# DAC_0.net
KiCad netlist of a schematic drawn in Altium Designer
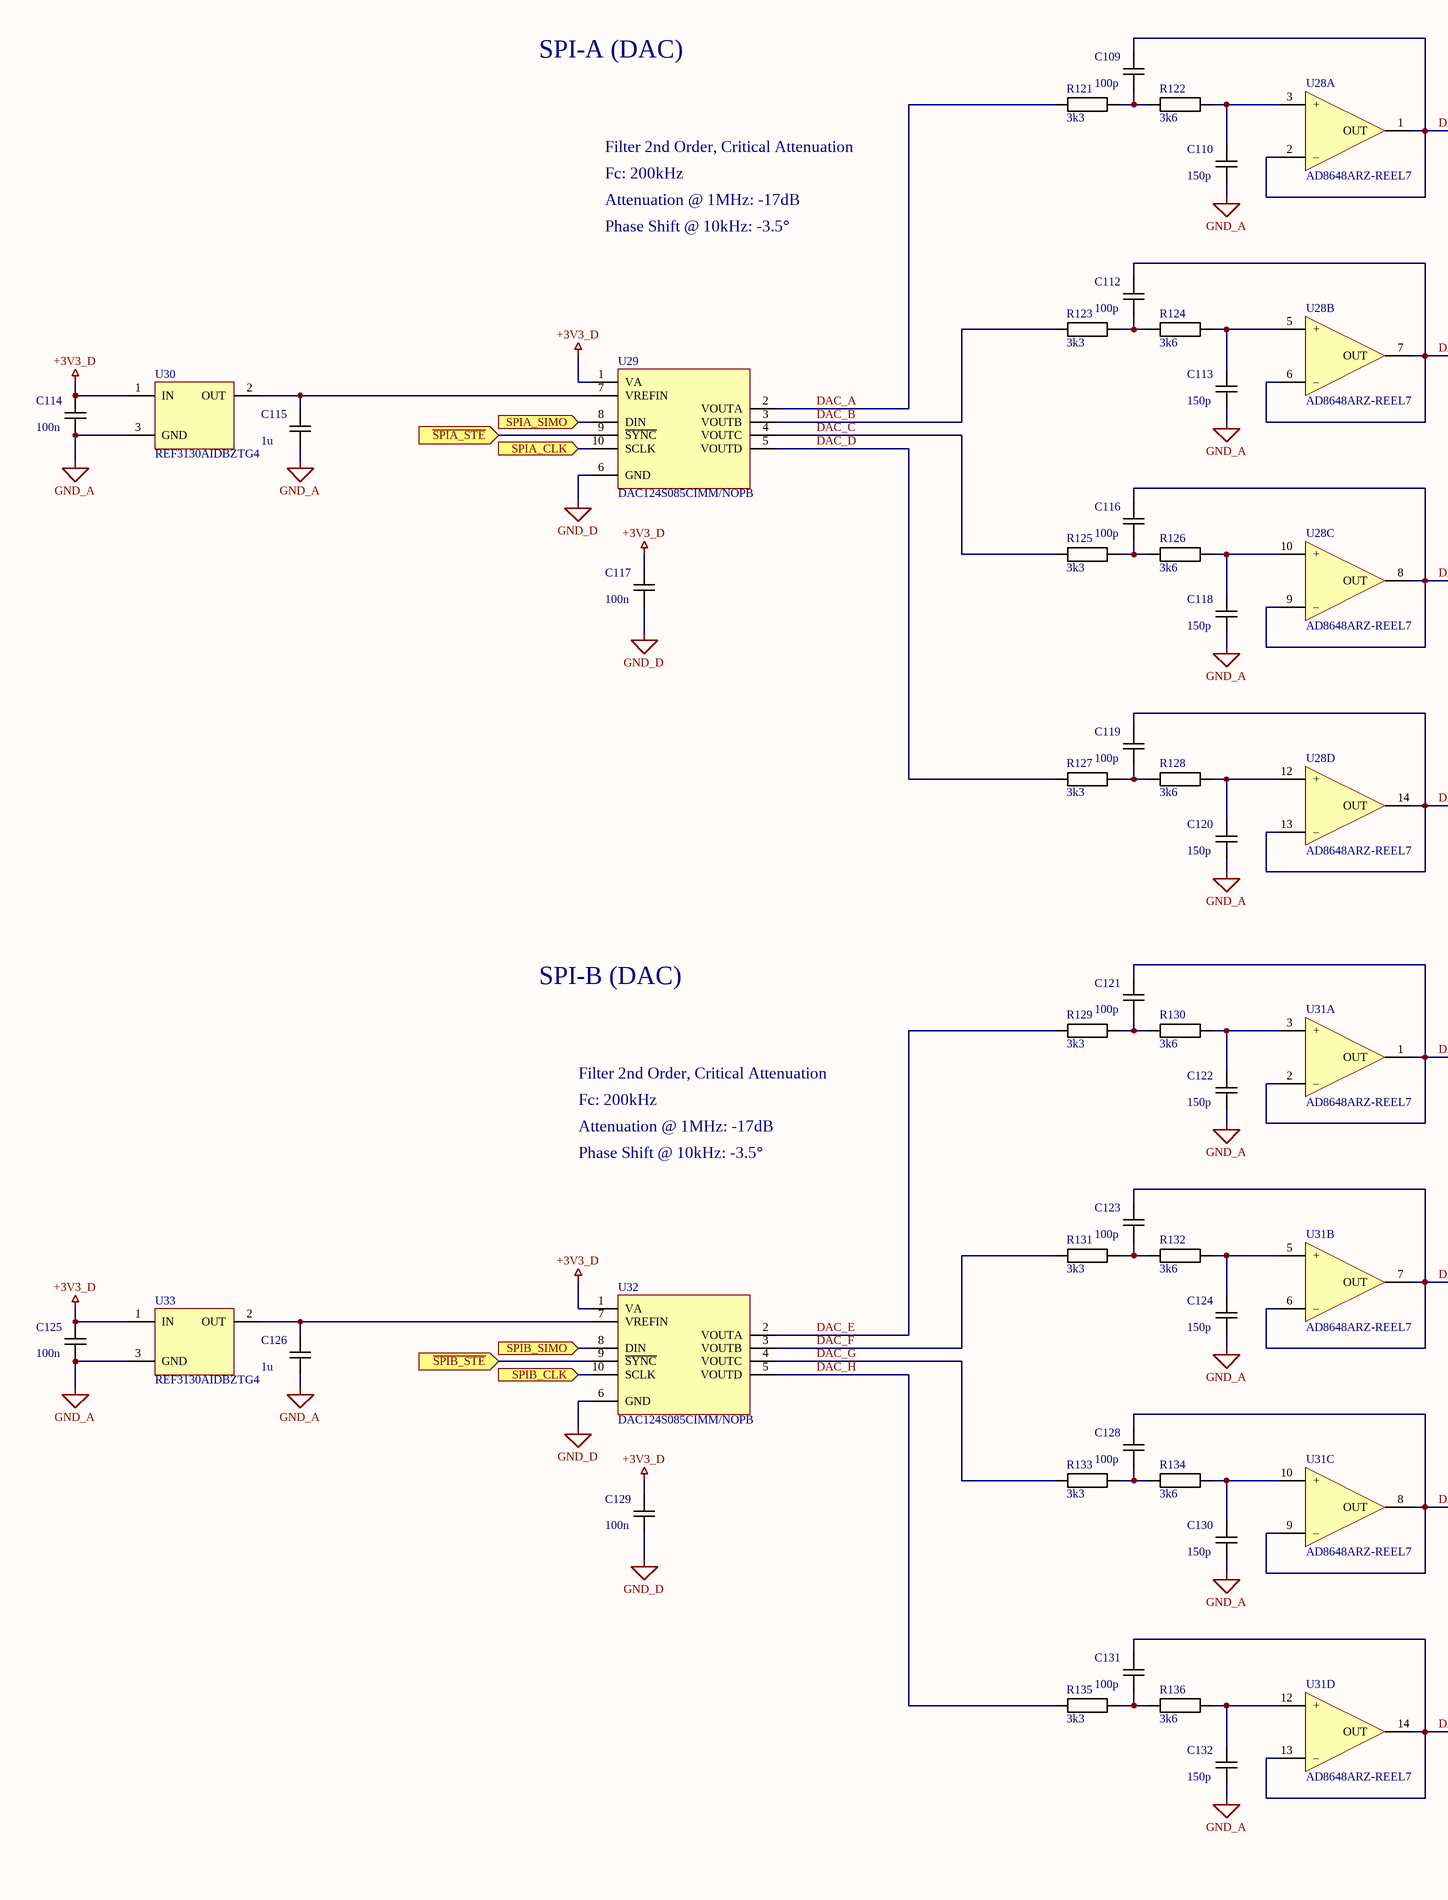
[diagram p0: DAC_0.SchDoc, left]
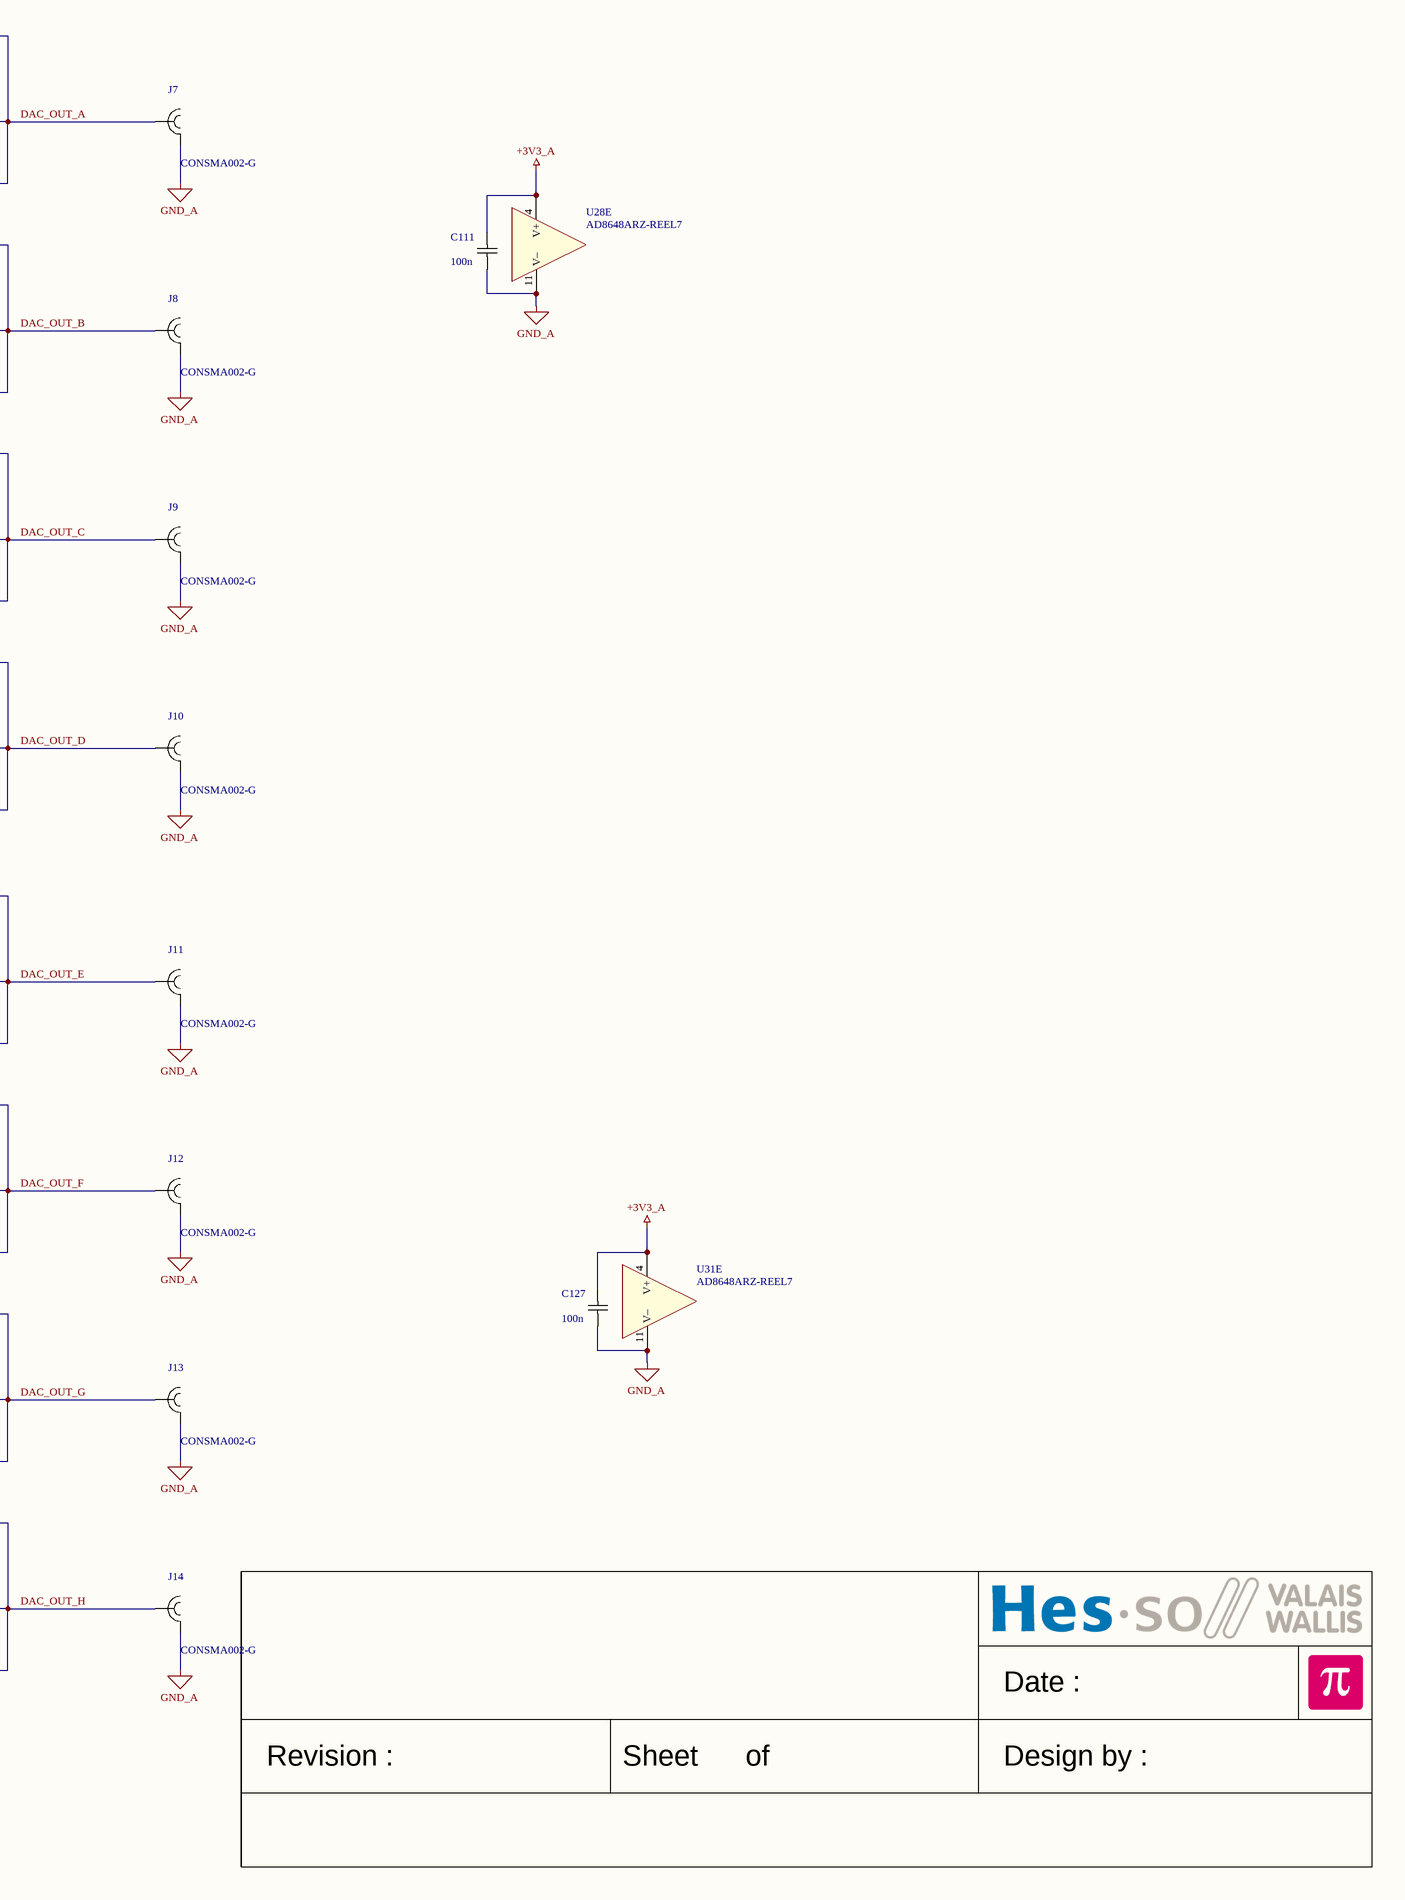
[diagram p1: DAC_0.SchDoc, right]

(export (version "E")
  (design (tool "Eeschema 10.0.6"))
  (components
    (comp (ref "C109")
      (value "100p")
      (footprint "CAPACITOR 2012 REFLOW")
      (description "Capacitor X7R 10% 50V 2012(0805)")
      (libsource (lib "Capacitor") (part "Capacitor"))
    )
    (comp (ref "C110")
      (value "150p")
      (footprint "CAPACITOR 2012 REFLOW")
      (description "Capacitor X7R 10% 50V 2012(0805)")
      (libsource (lib "Capacitor") (part "Capacitor"))
    )
    (comp (ref "C111")
      (value "100n")
      (footprint "CAPACITOR 1608 REFLOW")
      (description "Capacitor X7R 10% 50V 1608(0603)")
      (libsource (lib "Capacitor") (part "Capacitor"))
    )
    (comp (ref "C112")
      (value "100p")
      (footprint "CAPACITOR 2012 REFLOW")
      (description "Capacitor X7R 10% 50V 2012(0805)")
      (libsource (lib "Capacitor") (part "Capacitor"))
    )
    (comp (ref "C113")
      (value "150p")
      (footprint "CAPACITOR 2012 REFLOW")
      (description "Capacitor X7R 10% 50V 2012(0805)")
      (libsource (lib "Capacitor") (part "Capacitor"))
    )
    (comp (ref "C114")
      (value "100n")
      (footprint "CAPACITOR 2012 REFLOW")
      (description "Capacitor X7R 10% 50V 2012(0805)")
      (libsource (lib "Capacitor") (part "Capacitor"))
    )
    (comp (ref "C115")
      (value "1u")
      (footprint "CAPACITOR 2012 REFLOW")
      (description "Capacitor X7R 10% 10V 2012(0805)")
      (libsource (lib "Capacitor") (part "Capacitor"))
    )
    (comp (ref "C116")
      (value "100p")
      (footprint "CAPACITOR 2012 REFLOW")
      (description "Capacitor X7R 10% 50V 2012(0805)")
      (libsource (lib "Capacitor") (part "Capacitor"))
    )
    (comp (ref "C117")
      (value "100n")
      (footprint "CAPACITOR 1608 REFLOW")
      (description "Capacitor X7R 10% 50V 1608(0603)")
      (libsource (lib "Capacitor") (part "Capacitor"))
    )
    (comp (ref "C118")
      (value "150p")
      (footprint "CAPACITOR 2012 REFLOW")
      (description "Capacitor X7R 10% 50V 2012(0805)")
      (libsource (lib "Capacitor") (part "Capacitor"))
    )
    (comp (ref "C119")
      (value "100p")
      (footprint "CAPACITOR 2012 REFLOW")
      (description "Capacitor X7R 10% 50V 2012(0805)")
      (libsource (lib "Capacitor") (part "Capacitor"))
    )
    (comp (ref "C120")
      (value "150p")
      (footprint "CAPACITOR 2012 REFLOW")
      (description "Capacitor X7R 10% 50V 2012(0805)")
      (libsource (lib "Capacitor") (part "Capacitor"))
    )
    (comp (ref "C121")
      (value "100p")
      (footprint "CAPACITOR 2012 REFLOW")
      (description "Capacitor X7R 10% 50V 2012(0805)")
      (libsource (lib "Capacitor") (part "Capacitor"))
    )
    (comp (ref "C122")
      (value "150p")
      (footprint "CAPACITOR 2012 REFLOW")
      (description "Capacitor X7R 10% 50V 2012(0805)")
      (libsource (lib "Capacitor") (part "Capacitor"))
    )
    (comp (ref "C123")
      (value "100p")
      (footprint "CAPACITOR 2012 REFLOW")
      (description "Capacitor X7R 10% 50V 2012(0805)")
      (libsource (lib "Capacitor") (part "Capacitor"))
    )
    (comp (ref "C124")
      (value "150p")
      (footprint "CAPACITOR 2012 REFLOW")
      (description "Capacitor X7R 10% 50V 2012(0805)")
      (libsource (lib "Capacitor") (part "Capacitor"))
    )
    (comp (ref "C125")
      (value "100n")
      (footprint "CAPACITOR 2012 REFLOW")
      (description "Capacitor X7R 10% 50V 2012(0805)")
      (libsource (lib "Capacitor") (part "Capacitor"))
    )
    (comp (ref "C126")
      (value "1u")
      (footprint "CAPACITOR 2012 REFLOW")
      (description "Capacitor X7R 10% 10V 2012(0805)")
      (libsource (lib "Capacitor") (part "Capacitor"))
    )
    (comp (ref "C127")
      (value "100n")
      (footprint "CAPACITOR 1608 REFLOW")
      (description "Capacitor X7R 10% 50V 1608(0603)")
      (libsource (lib "Capacitor") (part "Capacitor"))
    )
    (comp (ref "C128")
      (value "100p")
      (footprint "CAPACITOR 2012 REFLOW")
      (description "Capacitor X7R 10% 50V 2012(0805)")
      (libsource (lib "Capacitor") (part "Capacitor"))
    )
    (comp (ref "C129")
      (value "100n")
      (footprint "CAPACITOR 1608 REFLOW")
      (description "Capacitor X7R 10% 50V 1608(0603)")
      (libsource (lib "Capacitor") (part "Capacitor"))
    )
    (comp (ref "C130")
      (value "150p")
      (footprint "CAPACITOR 2012 REFLOW")
      (description "Capacitor X7R 10% 50V 2012(0805)")
      (libsource (lib "Capacitor") (part "Capacitor"))
    )
    (comp (ref "C131")
      (value "100p")
      (footprint "CAPACITOR 2012 REFLOW")
      (description "Capacitor X7R 10% 50V 2012(0805)")
      (libsource (lib "Capacitor") (part "Capacitor"))
    )
    (comp (ref "C132")
      (value "150p")
      (footprint "CAPACITOR 2012 REFLOW")
      (description "Capacitor X7R 10% 50V 2012(0805)")
      (libsource (lib "Capacitor") (part "Capacitor"))
    )
    (comp (ref "J7")
      (value "CONSMA002-G")
      (footprint "SMA TH Right Angle Linx CONSMA002")
      (description "SMA TH RIGHT ANGLE LINX CONSMA002")
      (fields (field (name "MANUFACTURER") "Linx Technologies"))
      (libsource (lib "Connector") (part "SMA TH RIGHT ANGLE LINX CONSMA002"))
    )
    (comp (ref "J8")
      (value "CONSMA002-G")
      (footprint "SMA TH Right Angle Linx CONSMA002")
      (description "SMA TH RIGHT ANGLE LINX CONSMA002")
      (fields (field (name "MANUFACTURER") "Linx Technologies"))
      (libsource (lib "Connector") (part "SMA TH RIGHT ANGLE LINX CONSMA002"))
    )
    (comp (ref "J9")
      (value "CONSMA002-G")
      (footprint "SMA TH Right Angle Linx CONSMA002")
      (description "SMA TH RIGHT ANGLE LINX CONSMA002")
      (fields (field (name "MANUFACTURER") "Linx Technologies"))
      (libsource (lib "Connector") (part "SMA TH RIGHT ANGLE LINX CONSMA002"))
    )
    (comp (ref "J10")
      (value "CONSMA002-G")
      (footprint "SMA TH Right Angle Linx CONSMA002")
      (description "SMA TH RIGHT ANGLE LINX CONSMA002")
      (fields (field (name "MANUFACTURER") "Linx Technologies"))
      (libsource (lib "Connector") (part "SMA TH RIGHT ANGLE LINX CONSMA002"))
    )
    (comp (ref "J11")
      (value "CONSMA002-G")
      (footprint "SMA TH Right Angle Linx CONSMA002")
      (description "SMA TH RIGHT ANGLE LINX CONSMA002")
      (fields (field (name "MANUFACTURER") "Linx Technologies"))
      (libsource (lib "Connector") (part "SMA TH RIGHT ANGLE LINX CONSMA002"))
    )
    (comp (ref "J12")
      (value "CONSMA002-G")
      (footprint "SMA TH Right Angle Linx CONSMA002")
      (description "SMA TH RIGHT ANGLE LINX CONSMA002")
      (fields (field (name "MANUFACTURER") "Linx Technologies"))
      (libsource (lib "Connector") (part "SMA TH RIGHT ANGLE LINX CONSMA002"))
    )
    (comp (ref "J13")
      (value "CONSMA002-G")
      (footprint "SMA TH Right Angle Linx CONSMA002")
      (description "SMA TH RIGHT ANGLE LINX CONSMA002")
      (fields (field (name "MANUFACTURER") "Linx Technologies"))
      (libsource (lib "Connector") (part "SMA TH RIGHT ANGLE LINX CONSMA002"))
    )
    (comp (ref "J14")
      (value "CONSMA002-G")
      (footprint "SMA TH Right Angle Linx CONSMA002")
      (description "SMA TH RIGHT ANGLE LINX CONSMA002")
      (fields (field (name "MANUFACTURER") "Linx Technologies"))
      (libsource (lib "Connector") (part "SMA TH RIGHT ANGLE LINX CONSMA002"))
    )
    (comp (ref "R121")
      (value "3k3")
      (footprint "RESISTOR 2012 REFLOW")
      (description "Resistor 1% 50V 125mW 2012(0805)")
      (libsource (lib "Resistor") (part "Resistor"))
    )
    (comp (ref "R122")
      (value "3k6")
      (footprint "RESISTOR 2012 REFLOW")
      (description "Resistor 1% 50V 125mW 2012(0805)")
      (libsource (lib "Resistor") (part "Resistor"))
    )
    (comp (ref "R123")
      (value "3k3")
      (footprint "RESISTOR 2012 REFLOW")
      (description "Resistor 1% 50V 125mW 2012(0805)")
      (libsource (lib "Resistor") (part "Resistor"))
    )
    (comp (ref "R124")
      (value "3k6")
      (footprint "RESISTOR 2012 REFLOW")
      (description "Resistor 1% 50V 125mW 2012(0805)")
      (libsource (lib "Resistor") (part "Resistor"))
    )
    (comp (ref "R125")
      (value "3k3")
      (footprint "RESISTOR 2012 REFLOW")
      (description "Resistor 1% 50V 125mW 2012(0805)")
      (libsource (lib "Resistor") (part "Resistor"))
    )
    (comp (ref "R126")
      (value "3k6")
      (footprint "RESISTOR 2012 REFLOW")
      (description "Resistor 1% 50V 125mW 2012(0805)")
      (libsource (lib "Resistor") (part "Resistor"))
    )
    (comp (ref "R127")
      (value "3k3")
      (footprint "RESISTOR 2012 REFLOW")
      (description "Resistor 1% 50V 125mW 2012(0805)")
      (libsource (lib "Resistor") (part "Resistor"))
    )
    (comp (ref "R128")
      (value "3k6")
      (footprint "RESISTOR 2012 REFLOW")
      (description "Resistor 1% 50V 125mW 2012(0805)")
      (libsource (lib "Resistor") (part "Resistor"))
    )
    (comp (ref "R129")
      (value "3k3")
      (footprint "RESISTOR 2012 REFLOW")
      (description "Resistor 1% 50V 125mW 2012(0805)")
      (libsource (lib "Resistor") (part "Resistor"))
    )
    (comp (ref "R130")
      (value "3k6")
      (footprint "RESISTOR 2012 REFLOW")
      (description "Resistor 1% 50V 125mW 2012(0805)")
      (libsource (lib "Resistor") (part "Resistor"))
    )
    (comp (ref "R131")
      (value "3k3")
      (footprint "RESISTOR 2012 REFLOW")
      (description "Resistor 1% 50V 125mW 2012(0805)")
      (libsource (lib "Resistor") (part "Resistor"))
    )
    (comp (ref "R132")
      (value "3k6")
      (footprint "RESISTOR 2012 REFLOW")
      (description "Resistor 1% 50V 125mW 2012(0805)")
      (libsource (lib "Resistor") (part "Resistor"))
    )
    (comp (ref "R133")
      (value "3k3")
      (footprint "RESISTOR 2012 REFLOW")
      (description "Resistor 1% 50V 125mW 2012(0805)")
      (libsource (lib "Resistor") (part "Resistor"))
    )
    (comp (ref "R134")
      (value "3k6")
      (footprint "RESISTOR 2012 REFLOW")
      (description "Resistor 1% 50V 125mW 2012(0805)")
      (libsource (lib "Resistor") (part "Resistor"))
    )
    (comp (ref "R135")
      (value "3k3")
      (footprint "RESISTOR 2012 REFLOW")
      (description "Resistor 1% 50V 125mW 2012(0805)")
      (libsource (lib "Resistor") (part "Resistor"))
    )
    (comp (ref "R136")
      (value "3k6")
      (footprint "RESISTOR 2012 REFLOW")
      (description "Resistor 1% 50V 125mW 2012(0805)")
      (libsource (lib "Resistor") (part "Resistor"))
    )
    (comp (ref "U28")
      (value "AD8648ARZ-REEL7")
      (footprint "SO14 P1.27 C4.0X8.8 H1.75")
      (description "Generic quad OPA 14 pins")
      (fields (field (name "MANUFACTURER") "Analog Devices"))
      (libsource (lib "Amplifier") (part "OPA QUAD"))
    )
    (comp (ref "U29")
      (value "DAC124S085CIMM/NOPB")
      (footprint "VSSOP10 P0.5 C3.1X3.1 H1.1")
      (description "DAC124S085 12-Bit Micro Power Quad Digital-to-Analog Converter With Rail-to-Rail Output")
      (fields (field (name "MANUFACTURER") "Texas Instruments"))
      (libsource (lib "Converter") (part "DAC124S085CIMM"))
    )
    (comp (ref "U30")
      (value "REF3130AIDBZTG4")
      (footprint "SOT23 P0.95 C1.6x3.0 H1.3")
      (description "Generic Positive Voltage Reference")
      (libsource (lib "Regulator") (part "REFERENCE SOT23 IN,OUT,GND"))
    )
    (comp (ref "U31")
      (value "AD8648ARZ-REEL7")
      (footprint "SO14 P1.27 C4.0X8.8 H1.75")
      (description "Generic quad OPA 14 pins")
      (fields (field (name "MANUFACTURER") "Analog Devices"))
      (libsource (lib "Amplifier") (part "OPA QUAD"))
    )
    (comp (ref "U32")
      (value "DAC124S085CIMM/NOPB")
      (footprint "VSSOP10 P0.5 C3.1X3.1 H1.1")
      (description "DAC124S085 12-Bit Micro Power Quad Digital-to-Analog Converter With Rail-to-Rail Output")
      (fields (field (name "MANUFACTURER") "Texas Instruments"))
      (libsource (lib "Converter") (part "DAC124S085CIMM"))
    )
    (comp (ref "U33")
      (value "REF3130AIDBZTG4")
      (footprint "SOT23 P0.95 C1.6x3.0 H1.3")
      (description "Generic Positive Voltage Reference")
      (libsource (lib "Regulator") (part "REFERENCE SOT23 IN,OUT,GND"))
    )
  )
  (nets
    (net (code "1") (name "+3V3_A") (class "Default")
      (node (ref "C111") (pin "2") (pinfunction "2_2") (pintype "passive"))
      (node (ref "C127") (pin "2") (pinfunction "2_2") (pintype "passive"))
      (node (ref "U28") (pin "4") (pinfunction "V+_4") (pintype "passive"))
      (node (ref "U31") (pin "4") (pinfunction "V+_4") (pintype "passive"))
    )
    (net (code "2") (name "+3V3_D") (class "Default")
      (node (ref "C114") (pin "2") (pinfunction "2_2") (pintype "passive"))
      (node (ref "C117") (pin "2") (pinfunction "2_2") (pintype "passive"))
      (node (ref "C125") (pin "2") (pinfunction "2_2") (pintype "passive"))
      (node (ref "C129") (pin "2") (pinfunction "2_2") (pintype "passive"))
      (node (ref "U29") (pin "1") (pinfunction "VA_1") (pintype "passive"))
      (node (ref "U30") (pin "1") (pinfunction "IN_1") (pintype "passive"))
      (node (ref "U32") (pin "1") (pinfunction "VA_1") (pintype "passive"))
      (node (ref "U33") (pin "1") (pinfunction "IN_1") (pintype "passive"))
    )
    (net (code "3") (name "/DAC_A") (class "Default")
      (node (ref "R121") (pin "1") (pinfunction "1_1") (pintype "passive"))
      (node (ref "U29") (pin "2") (pinfunction "VOUTA_2") (pintype "passive"))
    )
    (net (code "4") (name "/DAC_B") (class "Default")
      (node (ref "R123") (pin "1") (pinfunction "1_1") (pintype "passive"))
      (node (ref "U29") (pin "3") (pinfunction "VOUTB_3") (pintype "passive"))
    )
    (net (code "5") (name "/DAC_C") (class "Default")
      (node (ref "R125") (pin "1") (pinfunction "1_1") (pintype "passive"))
      (node (ref "U29") (pin "4") (pinfunction "VOUTC_4") (pintype "passive"))
    )
    (net (code "6") (name "/DAC_D") (class "Default")
      (node (ref "R127") (pin "1") (pinfunction "1_1") (pintype "passive"))
      (node (ref "U29") (pin "5") (pinfunction "VOUTD_5") (pintype "passive"))
    )
    (net (code "7") (name "/DAC_E") (class "Default")
      (node (ref "R129") (pin "1") (pinfunction "1_1") (pintype "passive"))
      (node (ref "U32") (pin "2") (pinfunction "VOUTA_2") (pintype "passive"))
    )
    (net (code "8") (name "/DAC_F") (class "Default")
      (node (ref "R131") (pin "1") (pinfunction "1_1") (pintype "passive"))
      (node (ref "U32") (pin "3") (pinfunction "VOUTB_3") (pintype "passive"))
    )
    (net (code "9") (name "/DAC_G") (class "Default")
      (node (ref "R133") (pin "1") (pinfunction "1_1") (pintype "passive"))
      (node (ref "U32") (pin "4") (pinfunction "VOUTC_4") (pintype "passive"))
    )
    (net (code "10") (name "/DAC_H") (class "Default")
      (node (ref "R135") (pin "1") (pinfunction "1_1") (pintype "passive"))
      (node (ref "U32") (pin "5") (pinfunction "VOUTD_5") (pintype "passive"))
    )
    (net (code "11") (name "/DAC_OUT_A") (class "Default")
      (node (ref "C109") (pin "2") (pinfunction "2_2") (pintype "passive"))
      (node (ref "J7") (pin "1") (pinfunction "1_1") (pintype "passive"))
      (node (ref "U28") (pin "1") (pinfunction "OUT_1") (pintype "passive"))
      (node (ref "U28") (pin "2") (pinfunction "–_2") (pintype "passive"))
    )
    (net (code "12") (name "/DAC_OUT_B") (class "Default")
      (node (ref "C112") (pin "2") (pinfunction "2_2") (pintype "passive"))
      (node (ref "J8") (pin "1") (pinfunction "1_1") (pintype "passive"))
      (node (ref "U28") (pin "6") (pinfunction "–_6") (pintype "passive"))
      (node (ref "U28") (pin "7") (pinfunction "OUT_7") (pintype "passive"))
    )
    (net (code "13") (name "/DAC_OUT_C") (class "Default")
      (node (ref "C116") (pin "2") (pinfunction "2_2") (pintype "passive"))
      (node (ref "J9") (pin "1") (pinfunction "1_1") (pintype "passive"))
      (node (ref "U28") (pin "8") (pinfunction "OUT_8") (pintype "passive"))
      (node (ref "U28") (pin "9") (pinfunction "–_9") (pintype "passive"))
    )
    (net (code "14") (name "/DAC_OUT_D") (class "Default")
      (node (ref "C119") (pin "2") (pinfunction "2_2") (pintype "passive"))
      (node (ref "J10") (pin "1") (pinfunction "1_1") (pintype "passive"))
      (node (ref "U28") (pin "13") (pinfunction "–_13") (pintype "passive"))
      (node (ref "U28") (pin "14") (pinfunction "OUT_14") (pintype "passive"))
    )
    (net (code "15") (name "/DAC_OUT_E") (class "Default")
      (node (ref "C121") (pin "2") (pinfunction "2_2") (pintype "passive"))
      (node (ref "J11") (pin "1") (pinfunction "1_1") (pintype "passive"))
      (node (ref "U31") (pin "1") (pinfunction "OUT_1") (pintype "passive"))
      (node (ref "U31") (pin "2") (pinfunction "–_2") (pintype "passive"))
    )
    (net (code "16") (name "/DAC_OUT_F") (class "Default")
      (node (ref "C123") (pin "2") (pinfunction "2_2") (pintype "passive"))
      (node (ref "J12") (pin "1") (pinfunction "1_1") (pintype "passive"))
      (node (ref "U31") (pin "6") (pinfunction "–_6") (pintype "passive"))
      (node (ref "U31") (pin "7") (pinfunction "OUT_7") (pintype "passive"))
    )
    (net (code "17") (name "/DAC_OUT_G") (class "Default")
      (node (ref "C128") (pin "2") (pinfunction "2_2") (pintype "passive"))
      (node (ref "J13") (pin "1") (pinfunction "1_1") (pintype "passive"))
      (node (ref "U31") (pin "8") (pinfunction "OUT_8") (pintype "passive"))
      (node (ref "U31") (pin "9") (pinfunction "–_9") (pintype "passive"))
    )
    (net (code "18") (name "/DAC_OUT_H") (class "Default")
      (node (ref "C131") (pin "2") (pinfunction "2_2") (pintype "passive"))
      (node (ref "J14") (pin "1") (pinfunction "1_1") (pintype "passive"))
      (node (ref "U31") (pin "13") (pinfunction "–_13") (pintype "passive"))
      (node (ref "U31") (pin "14") (pinfunction "OUT_14") (pintype "passive"))
    )
    (net (code "19") (name "/SPIA_CLK") (class "Default")
      (node (ref "U29") (pin "10") (pinfunction "SCLK_10") (pintype "passive"))
    )
    (net (code "20") (name "/SPIA_SIMO") (class "Default")
      (node (ref "U29") (pin "8") (pinfunction "DIN_8") (pintype "passive"))
    )
    (net (code "21") (name "/SPIB_CLK") (class "Default")
      (node (ref "U32") (pin "10") (pinfunction "SCLK_10") (pintype "passive"))
    )
    (net (code "22") (name "/SPIB_SIMO") (class "Default")
      (node (ref "U32") (pin "8") (pinfunction "DIN_8") (pintype "passive"))
    )
    (net (code "23") (name "/~{SPIA_STE}") (class "Default")
      (node (ref "U29") (pin "9") (pinfunction "~{SYNC}_9") (pintype "passive"))
    )
    (net (code "24") (name "/~{SPIB_STE}") (class "Default")
      (node (ref "U32") (pin "9") (pinfunction "~{SYNC}_9") (pintype "passive"))
    )
    (net (code "25") (name "GND_A") (class "Default")
      (node (ref "C110") (pin "1") (pinfunction "1_1") (pintype "passive"))
      (node (ref "C111") (pin "1") (pinfunction "1_1") (pintype "passive"))
      (node (ref "C113") (pin "1") (pinfunction "1_1") (pintype "passive"))
      (node (ref "C114") (pin "1") (pinfunction "1_1") (pintype "passive"))
      (node (ref "C115") (pin "1") (pinfunction "1_1") (pintype "passive"))
      (node (ref "C118") (pin "1") (pinfunction "1_1") (pintype "passive"))
      (node (ref "C120") (pin "1") (pinfunction "1_1") (pintype "passive"))
      (node (ref "C122") (pin "1") (pinfunction "1_1") (pintype "passive"))
      (node (ref "C124") (pin "1") (pinfunction "1_1") (pintype "passive"))
      (node (ref "C125") (pin "1") (pinfunction "1_1") (pintype "passive"))
      (node (ref "C126") (pin "1") (pinfunction "1_1") (pintype "passive"))
      (node (ref "C127") (pin "1") (pinfunction "1_1") (pintype "passive"))
      (node (ref "C130") (pin "1") (pinfunction "1_1") (pintype "passive"))
      (node (ref "C132") (pin "1") (pinfunction "1_1") (pintype "passive"))
      (node (ref "J10") (pin "2") (pinfunction "2_2") (pintype "passive"))
      (node (ref "J11") (pin "2") (pinfunction "2_2") (pintype "passive"))
      (node (ref "J12") (pin "2") (pinfunction "2_2") (pintype "passive"))
      (node (ref "J13") (pin "2") (pinfunction "2_2") (pintype "passive"))
      (node (ref "J14") (pin "2") (pinfunction "2_2") (pintype "passive"))
      (node (ref "J7") (pin "2") (pinfunction "2_2") (pintype "passive"))
      (node (ref "J8") (pin "2") (pinfunction "2_2") (pintype "passive"))
      (node (ref "J9") (pin "2") (pinfunction "2_2") (pintype "passive"))
      (node (ref "U28") (pin "11") (pinfunction "V–_11") (pintype "passive"))
      (node (ref "U30") (pin "3") (pinfunction "GND_3") (pintype "passive"))
      (node (ref "U31") (pin "11") (pinfunction "V–_11") (pintype "passive"))
      (node (ref "U33") (pin "3") (pinfunction "GND_3") (pintype "passive"))
    )
    (net (code "26") (name "GND_D") (class "Default")
      (node (ref "C117") (pin "1") (pinfunction "1_1") (pintype "passive"))
      (node (ref "C129") (pin "1") (pinfunction "1_1") (pintype "passive"))
      (node (ref "U29") (pin "6") (pinfunction "GND_6") (pintype "passive"))
      (node (ref "U32") (pin "6") (pinfunction "GND_6") (pintype "passive"))
    )
    (net (code "27") (name "Net-(C109-Pad1)") (class "Default")
      (node (ref "C109") (pin "1") (pinfunction "1_1") (pintype "passive"))
      (node (ref "R121") (pin "2") (pinfunction "2_2") (pintype "passive"))
      (node (ref "R122") (pin "1") (pinfunction "1_1") (pintype "passive"))
    )
    (net (code "28") (name "Net-(C112-Pad1)") (class "Default")
      (node (ref "C112") (pin "1") (pinfunction "1_1") (pintype "passive"))
      (node (ref "R123") (pin "2") (pinfunction "2_2") (pintype "passive"))
      (node (ref "R124") (pin "1") (pinfunction "1_1") (pintype "passive"))
    )
    (net (code "29") (name "Net-(C116-Pad1)") (class "Default")
      (node (ref "C116") (pin "1") (pinfunction "1_1") (pintype "passive"))
      (node (ref "R125") (pin "2") (pinfunction "2_2") (pintype "passive"))
      (node (ref "R126") (pin "1") (pinfunction "1_1") (pintype "passive"))
    )
    (net (code "30") (name "Net-(C119-Pad1)") (class "Default")
      (node (ref "C119") (pin "1") (pinfunction "1_1") (pintype "passive"))
      (node (ref "R127") (pin "2") (pinfunction "2_2") (pintype "passive"))
      (node (ref "R128") (pin "1") (pinfunction "1_1") (pintype "passive"))
    )
    (net (code "31") (name "Net-(C121-Pad1)") (class "Default")
      (node (ref "C121") (pin "1") (pinfunction "1_1") (pintype "passive"))
      (node (ref "R129") (pin "2") (pinfunction "2_2") (pintype "passive"))
      (node (ref "R130") (pin "1") (pinfunction "1_1") (pintype "passive"))
    )
    (net (code "32") (name "Net-(C123-Pad1)") (class "Default")
      (node (ref "C123") (pin "1") (pinfunction "1_1") (pintype "passive"))
      (node (ref "R131") (pin "2") (pinfunction "2_2") (pintype "passive"))
      (node (ref "R132") (pin "1") (pinfunction "1_1") (pintype "passive"))
    )
    (net (code "33") (name "Net-(C128-Pad1)") (class "Default")
      (node (ref "C128") (pin "1") (pinfunction "1_1") (pintype "passive"))
      (node (ref "R133") (pin "2") (pinfunction "2_2") (pintype "passive"))
      (node (ref "R134") (pin "1") (pinfunction "1_1") (pintype "passive"))
    )
    (net (code "34") (name "Net-(C131-Pad1)") (class "Default")
      (node (ref "C131") (pin "1") (pinfunction "1_1") (pintype "passive"))
      (node (ref "R135") (pin "2") (pinfunction "2_2") (pintype "passive"))
      (node (ref "R136") (pin "1") (pinfunction "1_1") (pintype "passive"))
    )
    (net (code "35") (name "Net-(U28A-+)") (class "Default")
      (node (ref "C110") (pin "2") (pinfunction "2_2") (pintype "passive"))
      (node (ref "R122") (pin "2") (pinfunction "2_2") (pintype "passive"))
      (node (ref "U28") (pin "3") (pinfunction "+_3") (pintype "passive"))
    )
    (net (code "36") (name "Net-(U28B-+)") (class "Default")
      (node (ref "C113") (pin "2") (pinfunction "2_2") (pintype "passive"))
      (node (ref "R124") (pin "2") (pinfunction "2_2") (pintype "passive"))
      (node (ref "U28") (pin "5") (pinfunction "+_5") (pintype "passive"))
    )
    (net (code "37") (name "Net-(U28C-+)") (class "Default")
      (node (ref "C118") (pin "2") (pinfunction "2_2") (pintype "passive"))
      (node (ref "R126") (pin "2") (pinfunction "2_2") (pintype "passive"))
      (node (ref "U28") (pin "10") (pinfunction "+_10") (pintype "passive"))
    )
    (net (code "38") (name "Net-(U28D-+)") (class "Default")
      (node (ref "C120") (pin "2") (pinfunction "2_2") (pintype "passive"))
      (node (ref "R128") (pin "2") (pinfunction "2_2") (pintype "passive"))
      (node (ref "U28") (pin "12") (pinfunction "+_12") (pintype "passive"))
    )
    (net (code "39") (name "Net-(U29-VREFIN)") (class "Default")
      (node (ref "C115") (pin "2") (pinfunction "2_2") (pintype "passive"))
      (node (ref "U29") (pin "7") (pinfunction "VREFIN_7") (pintype "passive"))
      (node (ref "U30") (pin "2") (pinfunction "OUT_2") (pintype "passive"))
    )
    (net (code "40") (name "Net-(U31A-+)") (class "Default")
      (node (ref "C122") (pin "2") (pinfunction "2_2") (pintype "passive"))
      (node (ref "R130") (pin "2") (pinfunction "2_2") (pintype "passive"))
      (node (ref "U31") (pin "3") (pinfunction "+_3") (pintype "passive"))
    )
    (net (code "41") (name "Net-(U31B-+)") (class "Default")
      (node (ref "C124") (pin "2") (pinfunction "2_2") (pintype "passive"))
      (node (ref "R132") (pin "2") (pinfunction "2_2") (pintype "passive"))
      (node (ref "U31") (pin "5") (pinfunction "+_5") (pintype "passive"))
    )
    (net (code "42") (name "Net-(U31C-+)") (class "Default")
      (node (ref "C130") (pin "2") (pinfunction "2_2") (pintype "passive"))
      (node (ref "R134") (pin "2") (pinfunction "2_2") (pintype "passive"))
      (node (ref "U31") (pin "10") (pinfunction "+_10") (pintype "passive"))
    )
    (net (code "43") (name "Net-(U31D-+)") (class "Default")
      (node (ref "C132") (pin "2") (pinfunction "2_2") (pintype "passive"))
      (node (ref "R136") (pin "2") (pinfunction "2_2") (pintype "passive"))
      (node (ref "U31") (pin "12") (pinfunction "+_12") (pintype "passive"))
    )
    (net (code "44") (name "Net-(U32-VREFIN)") (class "Default")
      (node (ref "C126") (pin "2") (pinfunction "2_2") (pintype "passive"))
      (node (ref "U32") (pin "7") (pinfunction "VREFIN_7") (pintype "passive"))
      (node (ref "U33") (pin "2") (pinfunction "OUT_2") (pintype "passive"))
    )
  )
)
